# Connectors.net
KiCad netlist of a schematic drawn in Altium Designer
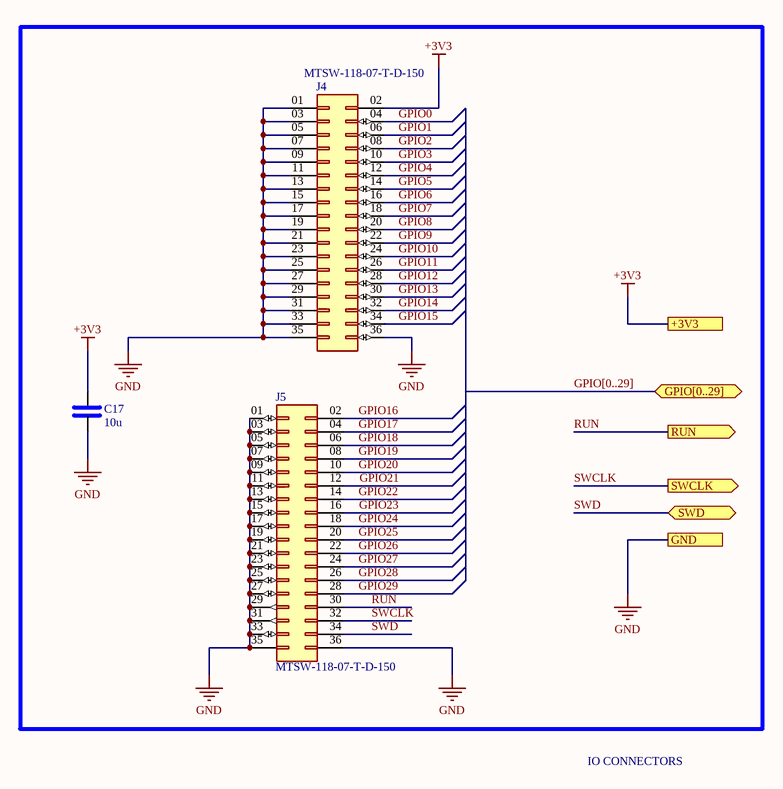
[diagram p0: Connectors.SchDoc]

(export (version "E")
  (design (tool "Eeschema 10.0.6"))
  (components
    (comp (ref "C17")
      (value "10u")
      (footprint "VJ0805")
      (fields
        (field (name "MANUFACTURER") "Murata")
        (field (name "MANUFACTURER PART NUMBER") "GRM21BR61E106KA73K")
      )
      (libsource (lib "Schlib") (part "0805 SMD Capacitor"))
    )
    (comp (ref "J4")
      (value "MTSW-118-07-T-D-150")
      (footprint "SAMTEC_MTSW-118-07-T-D-150")
      (libsource (lib "Integrated_Library") (part "MTSW-118-07-T-D-150"))
    )
    (comp (ref "J5")
      (value "MTSW-118-07-T-D-150")
      (footprint "SAMTEC_MTSW-118-07-T-D-150")
      (libsource (lib "Integrated_Library") (part "MTSW-118-07-T-D-150"))
    )
  )
  (nets
    (net (code "1") (name "+3V3") (class "Default")
      (node (ref "C17") (pin "2") (pinfunction "2_2") (pintype "passive"))
      (node (ref "J4") (pin "02") (pinfunction "02_02") (pintype "passive"))
    )
    (net (code "2") (name "/GPIO0") (class "Default")
      (node (ref "J4") (pin "04") (pinfunction "04_04") (pintype "passive"))
    )
    (net (code "3") (name "/GPIO1") (class "Default")
      (node (ref "J4") (pin "06") (pinfunction "06_06") (pintype "passive"))
    )
    (net (code "4") (name "/GPIO2") (class "Default")
      (node (ref "J4") (pin "08") (pinfunction "08_08") (pintype "passive"))
    )
    (net (code "5") (name "/GPIO3") (class "Default")
      (node (ref "J4") (pin "10") (pinfunction "10_10") (pintype "passive"))
    )
    (net (code "6") (name "/GPIO4") (class "Default")
      (node (ref "J4") (pin "12") (pinfunction "12_12") (pintype "passive"))
    )
    (net (code "7") (name "/GPIO5") (class "Default")
      (node (ref "J4") (pin "14") (pinfunction "14_14") (pintype "passive"))
    )
    (net (code "8") (name "/GPIO6") (class "Default")
      (node (ref "J4") (pin "16") (pinfunction "16_16") (pintype "passive"))
    )
    (net (code "9") (name "/GPIO7") (class "Default")
      (node (ref "J4") (pin "18") (pinfunction "18_18") (pintype "passive"))
    )
    (net (code "10") (name "/GPIO8") (class "Default")
      (node (ref "J4") (pin "20") (pinfunction "20_20") (pintype "passive"))
    )
    (net (code "11") (name "/GPIO9") (class "Default")
      (node (ref "J4") (pin "22") (pinfunction "22_22") (pintype "passive"))
    )
    (net (code "12") (name "/GPIO10") (class "Default")
      (node (ref "J4") (pin "24") (pinfunction "24_24") (pintype "passive"))
    )
    (net (code "13") (name "/GPIO11") (class "Default")
      (node (ref "J4") (pin "26") (pinfunction "26_26") (pintype "passive"))
    )
    (net (code "14") (name "/GPIO12") (class "Default")
      (node (ref "J4") (pin "28") (pinfunction "28_28") (pintype "passive"))
    )
    (net (code "15") (name "/GPIO13") (class "Default")
      (node (ref "J4") (pin "30") (pinfunction "30_30") (pintype "passive"))
    )
    (net (code "16") (name "/GPIO14") (class "Default")
      (node (ref "J4") (pin "32") (pinfunction "32_32") (pintype "passive"))
    )
    (net (code "17") (name "/GPIO15") (class "Default")
      (node (ref "J4") (pin "34") (pinfunction "34_34") (pintype "passive"))
    )
    (net (code "18") (name "/GPIO16") (class "Default")
      (node (ref "J5") (pin "02") (pinfunction "02_02") (pintype "passive"))
    )
    (net (code "19") (name "/GPIO17") (class "Default")
      (node (ref "J5") (pin "04") (pinfunction "04_04") (pintype "passive"))
    )
    (net (code "20") (name "/GPIO18") (class "Default")
      (node (ref "J5") (pin "06") (pinfunction "06_06") (pintype "passive"))
    )
    (net (code "21") (name "/GPIO19") (class "Default")
      (node (ref "J5") (pin "08") (pinfunction "08_08") (pintype "passive"))
    )
    (net (code "22") (name "/GPIO20") (class "Default")
      (node (ref "J5") (pin "10") (pinfunction "10_10") (pintype "passive"))
    )
    (net (code "23") (name "/GPIO21") (class "Default")
      (node (ref "J5") (pin "12") (pinfunction "12_12") (pintype "passive"))
    )
    (net (code "24") (name "/GPIO22") (class "Default")
      (node (ref "J5") (pin "14") (pinfunction "14_14") (pintype "passive"))
    )
    (net (code "25") (name "/GPIO23") (class "Default")
      (node (ref "J5") (pin "16") (pinfunction "16_16") (pintype "passive"))
    )
    (net (code "26") (name "/GPIO24") (class "Default")
      (node (ref "J5") (pin "18") (pinfunction "18_18") (pintype "passive"))
    )
    (net (code "27") (name "/GPIO25") (class "Default")
      (node (ref "J5") (pin "20") (pinfunction "20_20") (pintype "passive"))
    )
    (net (code "28") (name "/GPIO26") (class "Default")
      (node (ref "J5") (pin "22") (pinfunction "22_22") (pintype "passive"))
    )
    (net (code "29") (name "/GPIO27") (class "Default")
      (node (ref "J5") (pin "24") (pinfunction "24_24") (pintype "passive"))
    )
    (net (code "30") (name "/GPIO28") (class "Default")
      (node (ref "J5") (pin "26") (pinfunction "26_26") (pintype "passive"))
    )
    (net (code "31") (name "/GPIO29") (class "Default")
      (node (ref "J5") (pin "28") (pinfunction "28_28") (pintype "passive"))
    )
    (net (code "33") (name "/RUN") (class "Default")
      (node (ref "J5") (pin "30") (pinfunction "30_30") (pintype "passive"))
    )
    (net (code "34") (name "/SWCLK") (class "Default")
      (node (ref "J5") (pin "32") (pinfunction "32_32") (pintype "passive"))
    )
    (net (code "35") (name "/SWD") (class "Default")
      (node (ref "J5") (pin "34") (pinfunction "34_34") (pintype "passive"))
    )
    (net (code "36") (name "GND") (class "Default")
      (node (ref "C17") (pin "1") (pinfunction "1_1") (pintype "passive"))
      (node (ref "J4") (pin "01") (pinfunction "01_01") (pintype "bidirectional"))
      (node (ref "J4") (pin "03") (pinfunction "03_03") (pintype "bidirectional"))
      (node (ref "J4") (pin "05") (pinfunction "05_05") (pintype "bidirectional"))
      (node (ref "J4") (pin "07") (pinfunction "07_07") (pintype "bidirectional"))
      (node (ref "J4") (pin "09") (pinfunction "09_09") (pintype "bidirectional"))
      (node (ref "J4") (pin "11") (pinfunction "11_11") (pintype "bidirectional"))
      (node (ref "J4") (pin "13") (pinfunction "13_13") (pintype "bidirectional"))
      (node (ref "J4") (pin "15") (pinfunction "15_15") (pintype "bidirectional"))
      (node (ref "J4") (pin "17") (pinfunction "17_17") (pintype "bidirectional"))
      (node (ref "J4") (pin "19") (pinfunction "19_19") (pintype "bidirectional"))
      (node (ref "J4") (pin "21") (pinfunction "21_21") (pintype "bidirectional"))
      (node (ref "J4") (pin "23") (pinfunction "23_23") (pintype "bidirectional"))
      (node (ref "J4") (pin "25") (pinfunction "25_25") (pintype "bidirectional"))
      (node (ref "J4") (pin "27") (pinfunction "27_27") (pintype "bidirectional"))
      (node (ref "J4") (pin "29") (pinfunction "29_29") (pintype "output"))
      (node (ref "J4") (pin "31") (pinfunction "31_31") (pintype "output"))
      (node (ref "J4") (pin "33") (pinfunction "33_33") (pintype "bidirectional"))
      (node (ref "J4") (pin "35") (pinfunction "35_35") (pintype "passive"))
      (node (ref "J4") (pin "36") (pinfunction "36_36") (pintype "passive"))
      (node (ref "J5") (pin "01") (pinfunction "01_01") (pintype "bidirectional"))
      (node (ref "J5") (pin "03") (pinfunction "03_03") (pintype "bidirectional"))
      (node (ref "J5") (pin "05") (pinfunction "05_05") (pintype "bidirectional"))
      (node (ref "J5") (pin "07") (pinfunction "07_07") (pintype "bidirectional"))
      (node (ref "J5") (pin "09") (pinfunction "09_09") (pintype "bidirectional"))
      (node (ref "J5") (pin "11") (pinfunction "11_11") (pintype "bidirectional"))
      (node (ref "J5") (pin "13") (pinfunction "13_13") (pintype "bidirectional"))
      (node (ref "J5") (pin "15") (pinfunction "15_15") (pintype "bidirectional"))
      (node (ref "J5") (pin "17") (pinfunction "17_17") (pintype "bidirectional"))
      (node (ref "J5") (pin "19") (pinfunction "19_19") (pintype "bidirectional"))
      (node (ref "J5") (pin "21") (pinfunction "21_21") (pintype "bidirectional"))
      (node (ref "J5") (pin "23") (pinfunction "23_23") (pintype "bidirectional"))
      (node (ref "J5") (pin "25") (pinfunction "25_25") (pintype "bidirectional"))
      (node (ref "J5") (pin "27") (pinfunction "27_27") (pintype "bidirectional"))
      (node (ref "J5") (pin "29") (pinfunction "29_29") (pintype "output"))
      (node (ref "J5") (pin "31") (pinfunction "31_31") (pintype "output"))
      (node (ref "J5") (pin "33") (pinfunction "33_33") (pintype "bidirectional"))
      (node (ref "J5") (pin "35") (pinfunction "35_35") (pintype "passive"))
      (node (ref "J5") (pin "36") (pinfunction "36_36") (pintype "passive"))
    )
  )
)
